# OBC.net
KiCad netlist of a schematic drawn in EAGLE
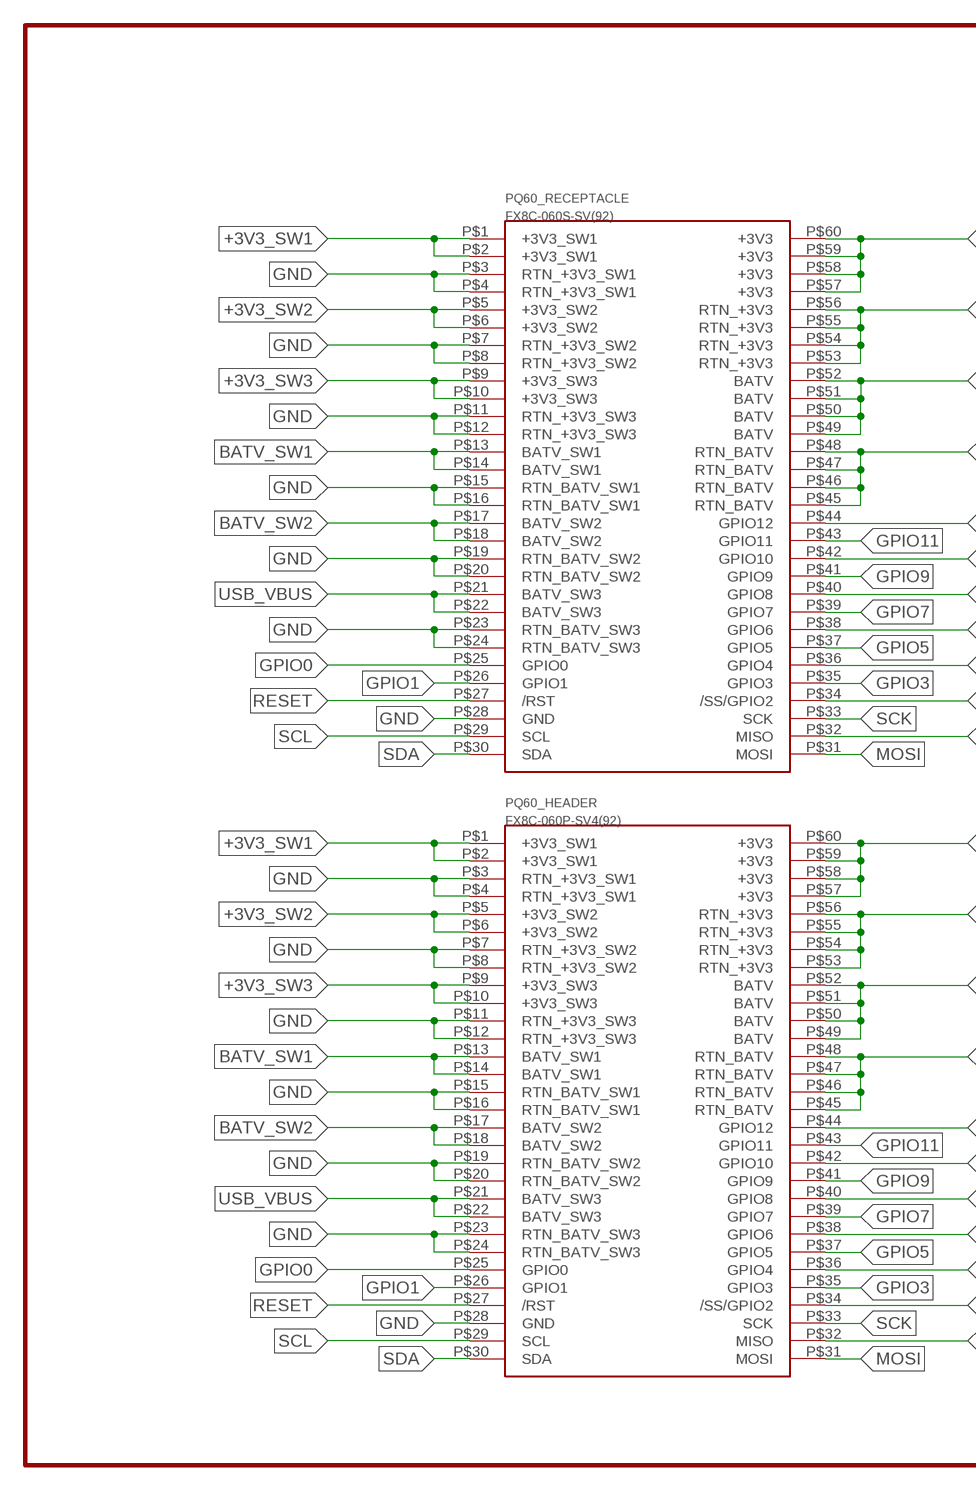
[diagram p0: schematic, sheet 1, part 1 of 2]
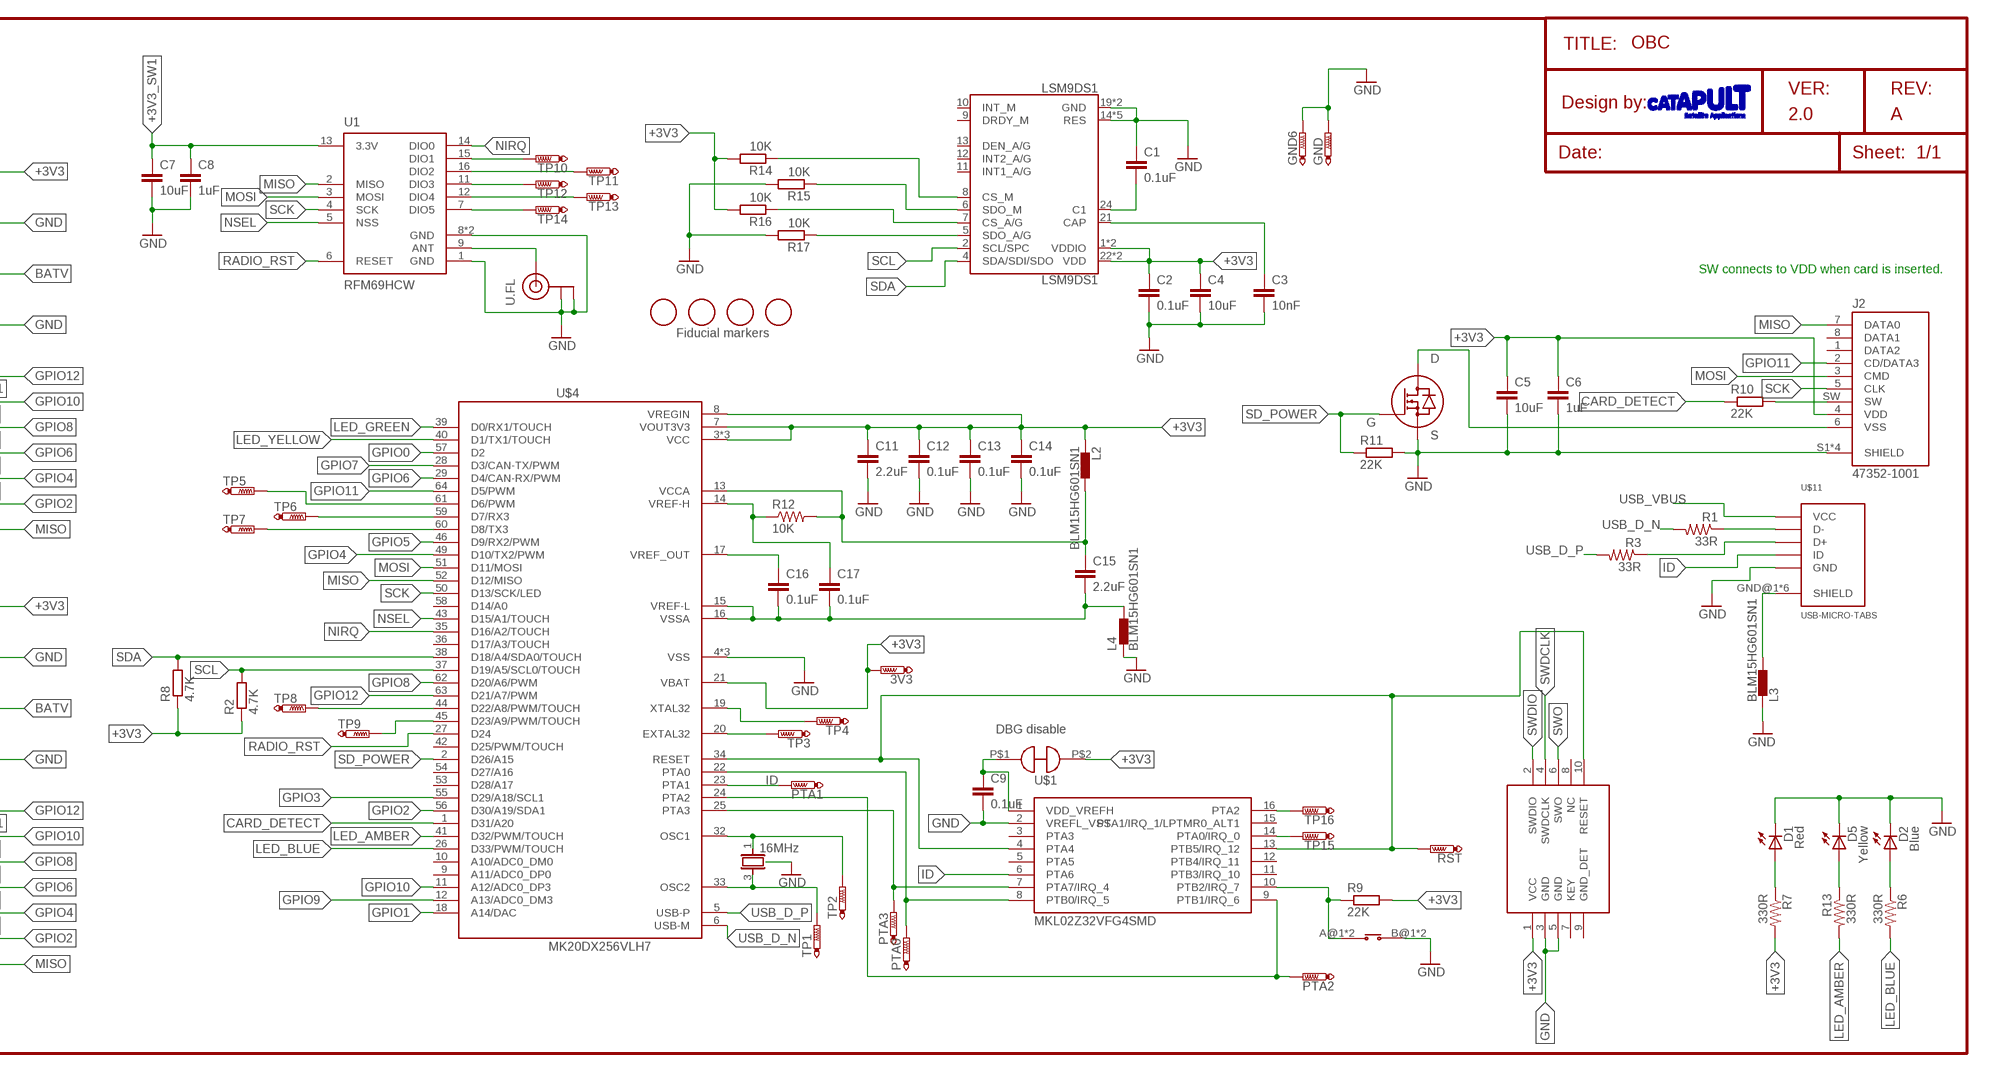
[diagram p1: schematic, sheet 1, part 2 of 2]

(export (version "E")
  (design (tool "Eeschema 10.0.6"))
  (components
    (comp (ref "3V3")
      (value "PTR1TP06R")
      (footprint "eagle-import:TP06R")
      (libsource (lib "eagle-import") (part "PTR1TP06R"))
    )
    (comp (ref "C1")
      (value "0.1uF")
      (footprint "eagle-import:C0402")
      (libsource (lib "eagle-import") (part "C-EUC0402"))
    )
    (comp (ref "C2")
      (value "0.1uF")
      (footprint "eagle-import:C0402")
      (libsource (lib "eagle-import") (part "C-EUC0402"))
    )
    (comp (ref "C3")
      (value "10nF")
      (footprint "eagle-import:C0402")
      (libsource (lib "eagle-import") (part "C-EUC0402"))
    )
    (comp (ref "C4")
      (value "10uF")
      (footprint "eagle-import:C0805")
      (libsource (lib "eagle-import") (part "C-EUC0805"))
    )
    (comp (ref "C5")
      (value "10uF")
      (footprint "eagle-import:C0805")
      (libsource (lib "eagle-import") (part "C-EUC0805"))
    )
    (comp (ref "C6")
      (value "1uF")
      (footprint "eagle-import:C0603")
      (libsource (lib "eagle-import") (part "C-EUC0603"))
    )
    (comp (ref "C7")
      (value "10uF")
      (footprint "eagle-import:C0805")
      (libsource (lib "eagle-import") (part "C-EUC0805"))
    )
    (comp (ref "C8")
      (value "1uF")
      (footprint "eagle-import:C0603")
      (libsource (lib "eagle-import") (part "C-EUC0603"))
    )
    (comp (ref "C9")
      (value "0.1uF")
      (footprint "eagle-import:C0402")
      (libsource (lib "eagle-import") (part "C-EUC0402"))
    )
    (comp (ref "C11")
      (value "2.2uF")
      (footprint "eagle-import:C0603")
      (libsource (lib "eagle-import") (part "C-EUC0603"))
    )
    (comp (ref "C12")
      (value "0.1uF")
      (footprint "eagle-import:C0402")
      (libsource (lib "eagle-import") (part "C-EUC0402"))
    )
    (comp (ref "C13")
      (value "0.1uF")
      (footprint "eagle-import:C0402")
      (libsource (lib "eagle-import") (part "C-EUC0402"))
    )
    (comp (ref "C14")
      (value "0.1uF")
      (footprint "eagle-import:C0402")
      (libsource (lib "eagle-import") (part "C-EUC0402"))
    )
    (comp (ref "C15")
      (value "2.2uF")
      (footprint "eagle-import:C0603")
      (libsource (lib "eagle-import") (part "C-EUC0603"))
    )
    (comp (ref "C16")
      (value "0.1uF")
      (footprint "eagle-import:C0402")
      (libsource (lib "eagle-import") (part "C-EUC0402"))
    )
    (comp (ref "C17")
      (value "0.1uF")
      (footprint "eagle-import:C0402")
      (libsource (lib "eagle-import") (part "C-EUC0402"))
    )
    (comp (ref "D1")
      (value "Red")
      (footprint "eagle-import:CHIPLED_0603")
      (libsource (lib "eagle-import") (part "LEDCHIPLED_0603"))
    )
    (comp (ref "D2")
      (value "Blue")
      (footprint "eagle-import:CHIPLED_0603")
      (libsource (lib "eagle-import") (part "LEDCHIPLED_0603"))
    )
    (comp (ref "D5")
      (value "Yellow")
      (footprint "eagle-import:CHIPLED_0603")
      (libsource (lib "eagle-import") (part "LEDCHIPLED_0603"))
    )
    (comp (ref "ERASE")
      (value "EVPAF7B70")
      (footprint "eagle-import:EVPAF7B70")
      (libsource (lib "eagle-import") (part "EVPAF7B70"))
    )
    (comp (ref "FD1")
      (value "FIDUCIAL")
      (footprint "eagle-import:FIDUCIAL_1MM")
      (libsource (lib "eagle-import") (part "FIDUCIAL"))
    )
    (comp (ref "FD2")
      (value "FIDUCIAL")
      (footprint "eagle-import:FIDUCIAL_1MM")
      (libsource (lib "eagle-import") (part "FIDUCIAL"))
    )
    (comp (ref "FD3")
      (value "FIDUCIAL")
      (footprint "eagle-import:FIDUCIAL_1MM")
      (libsource (lib "eagle-import") (part "FIDUCIAL"))
    )
    (comp (ref "FD4")
      (value "FIDUCIAL")
      (footprint "eagle-import:FIDUCIAL_1MM")
      (libsource (lib "eagle-import") (part "FIDUCIAL"))
    )
    (comp (ref "GND")
      (value "PTR1TP06R")
      (footprint "eagle-import:TP06R")
      (libsource (lib "eagle-import") (part "PTR1TP06R"))
    )
    (comp (ref "GND6")
      (value "PTR1TP06R")
      (footprint "eagle-import:TP06R")
      (libsource (lib "eagle-import") (part "PTR1TP06R"))
    )
    (comp (ref "J2")
      (value "47352-1001")
      (footprint "eagle-import:MOLEX_47352-1001")
      (fields (field (name "MF") "Molex") (field (name "MP") "473521001"))
      (libsource (lib "eagle-import") (part "47352-1001"))
    )
    (comp (ref "L2")
      (value "BLM15HG601SN1")
      (footprint "eagle-import:0402")
      (libsource (lib "eagle-import") (part "BLM15HG601SN1"))
    )
    (comp (ref "L3")
      (value "BLM15HG601SN1")
      (footprint "eagle-import:0402")
      (libsource (lib "eagle-import") (part "BLM15HG601SN1"))
    )
    (comp (ref "L4")
      (value "BLM15HG601SN1")
      (footprint "eagle-import:0402")
      (libsource (lib "eagle-import") (part "BLM15HG601SN1"))
    )
    (comp (ref "LSM9DS1")
      (value "LSM9DS1")
      (footprint "eagle-import:LGA24-8X4")
      (libsource (lib "eagle-import") (part "LSM9DS1"))
    )
    (comp (ref "NDK_NX3225SA")
      (value "16MHz")
      (footprint "eagle-import:4SMD_DFN_LCC")
      (libsource (lib "eagle-import") (part "NDKCRYSTAL"))
    )
    (comp (ref "PQ60_HEADER")
      (value "FX8C-060P-SV4(92)")
      (footprint "eagle-import:FX8C-060P-SV4(92)")
      (libsource (lib "eagle-import") (part "FX8C-060P-SV4(92)"))
    )
    (comp (ref "PQ60_RECEPTACLE")
      (value "FX8C-060S-SV(92)")
      (footprint "eagle-import:FX8C-060S-SV(92)")
      (libsource (lib "eagle-import") (part "FX8C-060S-SV(92)"))
    )
    (comp (ref "PTA0")
      (value "PTR1TP06R")
      (footprint "eagle-import:TP06R")
      (libsource (lib "eagle-import") (part "PTR1TP06R"))
    )
    (comp (ref "PTA1")
      (value "PTR1TP06R")
      (footprint "eagle-import:TP06R")
      (libsource (lib "eagle-import") (part "PTR1TP06R"))
    )
    (comp (ref "PTA2")
      (value "PTR1TP06R")
      (footprint "eagle-import:TP06R")
      (libsource (lib "eagle-import") (part "PTR1TP06R"))
    )
    (comp (ref "PTA3")
      (value "PTR1TP06R")
      (footprint "eagle-import:TP06R")
      (libsource (lib "eagle-import") (part "PTR1TP06R"))
    )
    (comp (ref "R1")
      (value "33R")
      (footprint "eagle-import:0603-RES")
      (libsource (lib "eagle-import") (part "RESISTOR0603-RES"))
    )
    (comp (ref "R2")
      (value "4.7K")
      (footprint "eagle-import:R0402")
      (libsource (lib "eagle-import") (part "R-EU_R0402"))
    )
    (comp (ref "R3")
      (value "33R")
      (footprint "eagle-import:0603-RES")
      (libsource (lib "eagle-import") (part "RESISTOR0603-RES"))
    )
    (comp (ref "R6")
      (value "330R")
      (footprint "eagle-import:0603-RES")
      (libsource (lib "eagle-import") (part "RESISTOR0603-RES"))
    )
    (comp (ref "R7")
      (value "330R")
      (footprint "eagle-import:0603-RES")
      (libsource (lib "eagle-import") (part "RESISTOR0603-RES"))
    )
    (comp (ref "R8")
      (value "4.7K")
      (footprint "eagle-import:R0402")
      (libsource (lib "eagle-import") (part "R-EU_R0402"))
    )
    (comp (ref "R9")
      (value "22K")
      (footprint "eagle-import:R0402")
      (libsource (lib "eagle-import") (part "R-EU_R0402"))
    )
    (comp (ref "R10")
      (value "22K")
      (footprint "eagle-import:R0402")
      (libsource (lib "eagle-import") (part "R-EU_R0402"))
    )
    (comp (ref "R11")
      (value "22K")
      (footprint "eagle-import:R0402")
      (libsource (lib "eagle-import") (part "R-EU_R0402"))
    )
    (comp (ref "R12")
      (value "10K")
      (footprint "eagle-import:0402-RES")
      (libsource (lib "eagle-import") (part "RESISTOR0402-RES"))
    )
    (comp (ref "R13")
      (value "330R")
      (footprint "eagle-import:0603-RES")
      (libsource (lib "eagle-import") (part "RESISTOR0603-RES"))
    )
    (comp (ref "R14")
      (value "10K")
      (footprint "eagle-import:R0402")
      (libsource (lib "eagle-import") (part "R-EU_R0402"))
    )
    (comp (ref "R15")
      (value "10K")
      (footprint "eagle-import:R0402")
      (libsource (lib "eagle-import") (part "R-EU_R0402"))
    )
    (comp (ref "R16")
      (value "10K")
      (footprint "eagle-import:R0402")
      (libsource (lib "eagle-import") (part "R-EU_R0402"))
    )
    (comp (ref "R17")
      (value "10K")
      (footprint "eagle-import:R0402")
      (libsource (lib "eagle-import") (part "R-EU_R0402"))
    )
    (comp (ref "RST")
      (value "PTR1TP06R")
      (footprint "eagle-import:TP06R")
      (libsource (lib "eagle-import") (part "PTR1TP06R"))
    )
    (comp (ref "SJ3")
      (value "SJNC")
      (footprint "eagle-import:SJNC")
      (libsource (lib "eagle-import") (part "SJNC"))
    )
    (comp (ref "TP1")
      (value "PTR1TP06R")
      (footprint "eagle-import:TP06R")
      (libsource (lib "eagle-import") (part "PTR1TP06R"))
    )
    (comp (ref "TP2")
      (value "PTR1TP06R")
      (footprint "eagle-import:TP06R")
      (libsource (lib "eagle-import") (part "PTR1TP06R"))
    )
    (comp (ref "TP3")
      (value "PTR1TP06R")
      (footprint "eagle-import:TP06R")
      (libsource (lib "eagle-import") (part "PTR1TP06R"))
    )
    (comp (ref "TP4")
      (value "PTR1TP06R")
      (footprint "eagle-import:TP06R")
      (libsource (lib "eagle-import") (part "PTR1TP06R"))
    )
    (comp (ref "TP5")
      (value "PTR1TP06R")
      (footprint "eagle-import:TP06R")
      (libsource (lib "eagle-import") (part "PTR1TP06R"))
    )
    (comp (ref "TP6")
      (value "PTR1TP06R")
      (footprint "eagle-import:TP06R")
      (libsource (lib "eagle-import") (part "PTR1TP06R"))
    )
    (comp (ref "TP7")
      (value "PTR1TP06R")
      (footprint "eagle-import:TP06R")
      (libsource (lib "eagle-import") (part "PTR1TP06R"))
    )
    (comp (ref "TP8")
      (value "PTR1TP06R")
      (footprint "eagle-import:TP06R")
      (libsource (lib "eagle-import") (part "PTR1TP06R"))
    )
    (comp (ref "TP9")
      (value "PTR1TP06R")
      (footprint "eagle-import:TP06R")
      (libsource (lib "eagle-import") (part "PTR1TP06R"))
    )
    (comp (ref "TP10")
      (value "PTR1TP06R")
      (footprint "eagle-import:TP06R")
      (libsource (lib "eagle-import") (part "PTR1TP06R"))
    )
    (comp (ref "TP11")
      (value "PTR1TP06R")
      (footprint "eagle-import:TP06R")
      (libsource (lib "eagle-import") (part "PTR1TP06R"))
    )
    (comp (ref "TP12")
      (value "PTR1TP06R")
      (footprint "eagle-import:TP06R")
      (libsource (lib "eagle-import") (part "PTR1TP06R"))
    )
    (comp (ref "TP13")
      (value "PTR1TP06R")
      (footprint "eagle-import:TP06R")
      (libsource (lib "eagle-import") (part "PTR1TP06R"))
    )
    (comp (ref "TP14")
      (value "PTR1TP06R")
      (footprint "eagle-import:TP06R")
      (libsource (lib "eagle-import") (part "PTR1TP06R"))
    )
    (comp (ref "TP15")
      (value "PTR1TP06R")
      (footprint "eagle-import:TP06R")
      (libsource (lib "eagle-import") (part "PTR1TP06R"))
    )
    (comp (ref "TP16")
      (value "PTR1TP06R")
      (footprint "eagle-import:TP06R")
      (libsource (lib "eagle-import") (part "PTR1TP06R"))
    )
    (comp (ref "U$1")
      (value "MKL02Z32VFG4SMD")
      (footprint "eagle-import:QFN16")
      (libsource (lib "eagle-import") (part "MKL02Z32VFG4SMD"))
    )
    (comp (ref "U$3")
      (value "PMV40UN2")
      (footprint "eagle-import:SOT23-3")
      (libsource (lib "eagle-import") (part "PMV40UN2"))
    )
    (comp (ref "U$4")
      (value "MK20DX256VLH7")
      (footprint "eagle-import:QFP50P1200X1200X160-64N")
      (libsource (lib "eagle-import") (part "MK20DX256VLH7"))
    )
    (comp (ref "U$9")
      (value "SWD_10_PIN")
      (footprint "eagle-import:SWD_10_PIN")
      (libsource (lib "eagle-import") (part "SWD_10_PIN"))
    )
    (comp (ref "U$11")
      (value "USB-MICRO-TABS")
      (footprint "eagle-import:USB-MICRO-TABS")
      (libsource (lib "eagle-import") (part "USB-MICRO-TABS"))
    )
    (comp (ref "U.FL")
      (value "U.FL")
      (footprint "eagle-import:U.FL")
      (libsource (lib "eagle-import") (part "U.FL"))
    )
    (comp (ref "U1")
      (value "RFM69HCW")
      (footprint "eagle-import:RFM69HCW-XXXS2")
      (libsource (lib "eagle-import") (part "RFM69HCW"))
    )
  )
  (nets
    (net (code "1") (name "+3V3") (class "Default")
      (node (ref "3V3") (pin "TP") (pinfunction "TP_TP") (pintype "input"))
      (node (ref "C11") (pin "1") (pinfunction "1_1") (pintype "passive"))
      (node (ref "C12") (pin "1") (pinfunction "1_1") (pintype "passive"))
      (node (ref "C13") (pin "1") (pinfunction "1_1") (pintype "passive"))
      (node (ref "C14") (pin "1") (pinfunction "1_1") (pintype "passive"))
      (node (ref "C2") (pin "1") (pinfunction "1_1") (pintype "passive"))
      (node (ref "C4") (pin "1") (pinfunction "1_1") (pintype "passive"))
      (node (ref "C5") (pin "1") (pinfunction "1_1") (pintype "passive"))
      (node (ref "C6") (pin "1") (pinfunction "1_1") (pintype "passive"))
      (node (ref "J2") (pin "4") (pinfunction "VDD_4") (pintype "passive"))
      (node (ref "L2") (pin "1") (pinfunction "1_1") (pintype "passive"))
      (node (ref "LSM9DS1") (pin "1") (pinfunction "VDDIO_1") (pintype "bidirectional"))
      (node (ref "LSM9DS1") (pin "22") (pinfunction "VDD_22") (pintype "bidirectional"))
      (node (ref "LSM9DS1") (pin "23") (pinfunction "VDD_23") (pintype "bidirectional"))
      (node (ref "LSM9DS1") (pin "3") (pinfunction "VDDIO_3") (pintype "bidirectional"))
      (node (ref "PQ60_HEADER") (pin "P$57") (pinfunction "+3V3_P$57") (pintype "power_in"))
      (node (ref "PQ60_HEADER") (pin "P$58") (pinfunction "+3V3_P$58") (pintype "power_in"))
      (node (ref "PQ60_HEADER") (pin "P$59") (pinfunction "+3V3_P$59") (pintype "power_in"))
      (node (ref "PQ60_HEADER") (pin "P$60") (pinfunction "+3V3_P$60") (pintype "power_in"))
      (node (ref "PQ60_RECEPTACLE") (pin "P$57") (pinfunction "+3V3_P$57") (pintype "power_in"))
      (node (ref "PQ60_RECEPTACLE") (pin "P$58") (pinfunction "+3V3_P$58") (pintype "power_in"))
      (node (ref "PQ60_RECEPTACLE") (pin "P$59") (pinfunction "+3V3_P$59") (pintype "power_in"))
      (node (ref "PQ60_RECEPTACLE") (pin "P$60") (pinfunction "+3V3_P$60") (pintype "power_in"))
      (node (ref "R14") (pin "2") (pinfunction "2_2") (pintype "passive"))
      (node (ref "R16") (pin "2") (pinfunction "2_2") (pintype "passive"))
      (node (ref "R2") (pin "1") (pinfunction "1_1") (pintype "passive"))
      (node (ref "R7") (pin "2") (pinfunction "2_2") (pintype "passive"))
      (node (ref "R8") (pin "1") (pinfunction "1_1") (pintype "passive"))
      (node (ref "R9") (pin "2") (pinfunction "2_2") (pintype "passive"))
      (node (ref "SJ3") (pin "P$2") (pinfunction "P$2_P$2") (pintype "bidirectional"))
      (node (ref "U$4") (pin "21") (pinfunction "VBAT_21") (pintype "bidirectional"))
      (node (ref "U$4") (pin "3") (pinfunction "VCC_3") (pintype "bidirectional"))
      (node (ref "U$4") (pin "30") (pinfunction "VCC_30") (pintype "bidirectional"))
      (node (ref "U$4") (pin "48") (pinfunction "VCC_48") (pintype "bidirectional"))
      (node (ref "U$4") (pin "7") (pinfunction "VOUT3V3_7") (pintype "bidirectional"))
      (node (ref "U$4") (pin "8") (pinfunction "VREGIN_8") (pintype "bidirectional"))
      (node (ref "U$9") (pin "1") (pinfunction "VCC_1") (pintype "bidirectional"))
    )
    (net (code "2") (name "+3V3_SW1") (class "Default")
      (node (ref "C7") (pin "1") (pinfunction "1_1") (pintype "passive"))
      (node (ref "C8") (pin "1") (pinfunction "1_1") (pintype "passive"))
      (node (ref "PQ60_HEADER") (pin "P$1") (pinfunction "+3V3_SW1_P$1") (pintype "power_in"))
      (node (ref "PQ60_HEADER") (pin "P$2") (pinfunction "+3V3_SW1_P$2") (pintype "power_in"))
      (node (ref "PQ60_RECEPTACLE") (pin "P$1") (pinfunction "+3V3_SW1_P$1") (pintype "power_in"))
      (node (ref "PQ60_RECEPTACLE") (pin "P$2") (pinfunction "+3V3_SW1_P$2") (pintype "power_in"))
      (node (ref "U1") (pin "13") (pinfunction "3.3V_13") (pintype "power_in"))
    )
    (net (code "3") (name "+3V3_SW2") (class "Default")
      (node (ref "PQ60_HEADER") (pin "P$5") (pinfunction "+3V3_SW2_P$5") (pintype "power_in"))
      (node (ref "PQ60_HEADER") (pin "P$6") (pinfunction "+3V3_SW2_P$6") (pintype "power_in"))
      (node (ref "PQ60_RECEPTACLE") (pin "P$5") (pinfunction "+3V3_SW2_P$5") (pintype "power_in"))
      (node (ref "PQ60_RECEPTACLE") (pin "P$6") (pinfunction "+3V3_SW2_P$6") (pintype "power_in"))
    )
    (net (code "4") (name "+3V3_SW3") (class "Default")
      (node (ref "PQ60_HEADER") (pin "P$10") (pinfunction "+3V3_SW3_P$10") (pintype "power_in"))
      (node (ref "PQ60_HEADER") (pin "P$9") (pinfunction "+3V3_SW3_P$9") (pintype "power_in"))
      (node (ref "PQ60_RECEPTACLE") (pin "P$10") (pinfunction "+3V3_SW3_P$10") (pintype "power_in"))
      (node (ref "PQ60_RECEPTACLE") (pin "P$9") (pinfunction "+3V3_SW3_P$9") (pintype "power_in"))
    )
    (net (code "5") (name "BATV") (class "Default")
      (node (ref "PQ60_HEADER") (pin "P$49") (pinfunction "BATV_P$49") (pintype "power_in"))
      (node (ref "PQ60_HEADER") (pin "P$50") (pinfunction "BATV_P$50") (pintype "power_in"))
      (node (ref "PQ60_HEADER") (pin "P$51") (pinfunction "BATV_P$51") (pintype "power_in"))
      (node (ref "PQ60_HEADER") (pin "P$52") (pinfunction "BATV_P$52") (pintype "power_in"))
      (node (ref "PQ60_RECEPTACLE") (pin "P$49") (pinfunction "BATV_P$49") (pintype "power_in"))
      (node (ref "PQ60_RECEPTACLE") (pin "P$50") (pinfunction "BATV_P$50") (pintype "power_in"))
      (node (ref "PQ60_RECEPTACLE") (pin "P$51") (pinfunction "BATV_P$51") (pintype "power_in"))
      (node (ref "PQ60_RECEPTACLE") (pin "P$52") (pinfunction "BATV_P$52") (pintype "power_in"))
    )
    (net (code "6") (name "BATV_SW1") (class "Default")
      (node (ref "PQ60_HEADER") (pin "P$13") (pinfunction "BATV_SW1_P$13") (pintype "power_in"))
      (node (ref "PQ60_HEADER") (pin "P$14") (pinfunction "BATV_SW1_P$14") (pintype "power_in"))
      (node (ref "PQ60_RECEPTACLE") (pin "P$13") (pinfunction "BATV_SW1_P$13") (pintype "power_in"))
      (node (ref "PQ60_RECEPTACLE") (pin "P$14") (pinfunction "BATV_SW1_P$14") (pintype "power_in"))
    )
    (net (code "7") (name "BATV_SW2") (class "Default")
      (node (ref "PQ60_HEADER") (pin "P$17") (pinfunction "BATV_SW2_P$17") (pintype "power_in"))
      (node (ref "PQ60_HEADER") (pin "P$18") (pinfunction "BATV_SW2_P$18") (pintype "power_in"))
      (node (ref "PQ60_RECEPTACLE") (pin "P$17") (pinfunction "BATV_SW2_P$17") (pintype "power_in"))
      (node (ref "PQ60_RECEPTACLE") (pin "P$18") (pinfunction "BATV_SW2_P$18") (pintype "power_in"))
    )
    (net (code "8") (name "CARD_DETECT") (class "Default")
      (node (ref "R10") (pin "1") (pinfunction "1_1") (pintype "passive"))
      (node (ref "U$4") (pin "1") (pinfunction "D31/A20_1") (pintype "bidirectional"))
    )
    (net (code "9") (name "GND") (class "Default")
      (node (ref "C1") (pin "1") (pinfunction "1_1") (pintype "passive"))
      (node (ref "C11") (pin "2") (pinfunction "2_2") (pintype "passive"))
      (node (ref "C12") (pin "2") (pinfunction "2_2") (pintype "passive"))
      (node (ref "C13") (pin "2") (pinfunction "2_2") (pintype "passive"))
      (node (ref "C14") (pin "2") (pinfunction "2_2") (pintype "passive"))
      (node (ref "C2") (pin "2") (pinfunction "2_2") (pintype "passive"))
      (node (ref "C3") (pin "2") (pinfunction "2_2") (pintype "passive"))
      (node (ref "C4") (pin "2") (pinfunction "2_2") (pintype "passive"))
      (node (ref "C5") (pin "2") (pinfunction "2_2") (pintype "passive"))
      (node (ref "C6") (pin "2") (pinfunction "2_2") (pintype "passive"))
      (node (ref "C7") (pin "2") (pinfunction "2_2") (pintype "passive"))
      (node (ref "C8") (pin "2") (pinfunction "2_2") (pintype "passive"))
      (node (ref "C9") (pin "2") (pinfunction "2_2") (pintype "passive"))
      (node (ref "D1") (pin "C") (pinfunction "C_C") (pintype "passive"))
      (node (ref "D2") (pin "C") (pinfunction "C_C") (pintype "passive"))
      (node (ref "D5") (pin "C") (pinfunction "C_C") (pintype "passive"))
      (node (ref "ERASE") (pin "B@1") (pinfunction "P$2_B@1") (pintype "bidirectional"))
      (node (ref "ERASE") (pin "B@2") (pinfunction "P$2_B@2") (pintype "bidirectional"))
      (node (ref "GND") (pin "TP") (pinfunction "TP_TP") (pintype "input"))
      (node (ref "GND6") (pin "TP") (pinfunction "TP_TP") (pintype "input"))
      (node (ref "J2") (pin "S1") (pinfunction "SHIELD_S1") (pintype "passive"))
      (node (ref "J2") (pin "S2") (pinfunction "SHIELD_S2") (pintype "passive"))
      (node (ref "J2") (pin "S3") (pinfunction "SHIELD_S3") (pintype "passive"))
      (node (ref "J2") (pin "S4") (pinfunction "SHIELD_S4") (pintype "passive"))
      (node (ref "L3") (pin "1") (pinfunction "1_1") (pintype "passive"))
      (node (ref "L4") (pin "1") (pinfunction "1_1") (pintype "passive"))
      (node (ref "LSM9DS1") (pin "14") (pinfunction "RES_14") (pintype "bidirectional"))
      (node (ref "LSM9DS1") (pin "15") (pinfunction "RES_15") (pintype "bidirectional"))
      (node (ref "LSM9DS1") (pin "16") (pinfunction "RES_16") (pintype "bidirectional"))
      (node (ref "LSM9DS1") (pin "17") (pinfunction "RES_17") (pintype "bidirectional"))
      (node (ref "LSM9DS1") (pin "18") (pinfunction "RES_18") (pintype "bidirectional"))
      (node (ref "LSM9DS1") (pin "19") (pinfunction "GND_19") (pintype "bidirectional"))
      (node (ref "LSM9DS1") (pin "20") (pinfunction "GND_20") (pintype "bidirectional"))
      (node (ref "NDK_NX3225SA") (pin "GND") (pinfunction "GND_GND") (pintype "bidirectional"))
      (node (ref "NDK_NX3225SA") (pin "GND@1") (pinfunction "GND_GND@1") (pintype "bidirectional"))
      (node (ref "NDK_NX3225SA") (pin "GND@2") (pinfunction "GND_GND@2") (pintype "bidirectional"))
      (node (ref "PQ60_HEADER") (pin "P$11") (pinfunction "RTN_+3V3_SW3_P$11") (pintype "power_in"))
      (node (ref "PQ60_HEADER") (pin "P$12") (pinfunction "RTN_+3V3_SW3_P$12") (pintype "power_in"))
      (node (ref "PQ60_HEADER") (pin "P$15") (pinfunction "RTN_BATV_SW1_P$15") (pintype "power_in"))
      (node (ref "PQ60_HEADER") (pin "P$16") (pinfunction "RTN_BATV_SW1_P$16") (pintype "power_in"))
      (node (ref "PQ60_HEADER") (pin "P$19") (pinfunction "RTN_BATV_SW2_P$19") (pintype "power_in"))
      (node (ref "PQ60_HEADER") (pin "P$20") (pinfunction "RTN_BATV_SW2_P$20") (pintype "power_in"))
      (node (ref "PQ60_HEADER") (pin "P$23") (pinfunction "RTN_BATV_SW3_P$23") (pintype "power_in"))
      (node (ref "PQ60_HEADER") (pin "P$24") (pinfunction "RTN_BATV_SW3_P$24") (pintype "power_in"))
      (node (ref "PQ60_HEADER") (pin "P$28") (pinfunction "GND_P$28") (pintype "bidirectional"))
      (node (ref "PQ60_HEADER") (pin "P$3") (pinfunction "RTN_+3V3_SW1_P$3") (pintype "power_in"))
      (node (ref "PQ60_HEADER") (pin "P$4") (pinfunction "RTN_+3V3_SW1_P$4") (pintype "power_in"))
      (node (ref "PQ60_HEADER") (pin "P$45") (pinfunction "RTN_BATV_P$45") (pintype "power_in"))
      (node (ref "PQ60_HEADER") (pin "P$46") (pinfunction "RTN_BATV_P$46") (pintype "power_in"))
      (node (ref "PQ60_HEADER") (pin "P$47") (pinfunction "RTN_BATV_P$47") (pintype "power_in"))
      (node (ref "PQ60_HEADER") (pin "P$48") (pinfunction "RTN_BATV_P$48") (pintype "power_in"))
      (node (ref "PQ60_HEADER") (pin "P$53") (pinfunction "RTN_+3V3_P$53") (pintype "power_in"))
      (node (ref "PQ60_HEADER") (pin "P$54") (pinfunction "RTN_+3V3_P$54") (pintype "power_in"))
      (node (ref "PQ60_HEADER") (pin "P$55") (pinfunction "RTN_+3V3_P$55") (pintype "power_in"))
      (node (ref "PQ60_HEADER") (pin "P$56") (pinfunction "RTN_+3V3_P$56") (pintype "power_in"))
      (node (ref "PQ60_HEADER") (pin "P$7") (pinfunction "RTN_+3V3_SW2_P$7") (pintype "power_in"))
      (node (ref "PQ60_HEADER") (pin "P$8") (pinfunction "RTN_+3V3_SW2_P$8") (pintype "power_in"))
      (node (ref "PQ60_RECEPTACLE") (pin "P$11") (pinfunction "RTN_+3V3_SW3_P$11") (pintype "power_in"))
      (node (ref "PQ60_RECEPTACLE") (pin "P$12") (pinfunction "RTN_+3V3_SW3_P$12") (pintype "power_in"))
      (node (ref "PQ60_RECEPTACLE") (pin "P$15") (pinfunction "RTN_BATV_SW1_P$15") (pintype "power_in"))
      (node (ref "PQ60_RECEPTACLE") (pin "P$16") (pinfunction "RTN_BATV_SW1_P$16") (pintype "power_in"))
      (node (ref "PQ60_RECEPTACLE") (pin "P$19") (pinfunction "RTN_BATV_SW2_P$19") (pintype "power_in"))
      (node (ref "PQ60_RECEPTACLE") (pin "P$20") (pinfunction "RTN_BATV_SW2_P$20") (pintype "power_in"))
      (node (ref "PQ60_RECEPTACLE") (pin "P$23") (pinfunction "RTN_BATV_SW3_P$23") (pintype "power_in"))
      (node (ref "PQ60_RECEPTACLE") (pin "P$24") (pinfunction "RTN_BATV_SW3_P$24") (pintype "power_in"))
      (node (ref "PQ60_RECEPTACLE") (pin "P$28") (pinfunction "GND_P$28") (pintype "bidirectional"))
      (node (ref "PQ60_RECEPTACLE") (pin "P$3") (pinfunction "RTN_+3V3_SW1_P$3") (pintype "power_in"))
      (node (ref "PQ60_RECEPTACLE") (pin "P$4") (pinfunction "RTN_+3V3_SW1_P$4") (pintype "power_in"))
      (node (ref "PQ60_RECEPTACLE") (pin "P$45") (pinfunction "RTN_BATV_P$45") (pintype "power_in"))
      (node (ref "PQ60_RECEPTACLE") (pin "P$46") (pinfunction "RTN_BATV_P$46") (pintype "power_in"))
      (node (ref "PQ60_RECEPTACLE") (pin "P$47") (pinfunction "RTN_BATV_P$47") (pintype "power_in"))
      (node (ref "PQ60_RECEPTACLE") (pin "P$48") (pinfunction "RTN_BATV_P$48") (pintype "power_in"))
      (node (ref "PQ60_RECEPTACLE") (pin "P$53") (pinfunction "RTN_+3V3_P$53") (pintype "power_in"))
      (node (ref "PQ60_RECEPTACLE") (pin "P$54") (pinfunction "RTN_+3V3_P$54") (pintype "power_in"))
      (node (ref "PQ60_RECEPTACLE") (pin "P$55") (pinfunction "RTN_+3V3_P$55") (pintype "power_in"))
      (node (ref "PQ60_RECEPTACLE") (pin "P$56") (pinfunction "RTN_+3V3_P$56") (pintype "power_in"))
      (node (ref "PQ60_RECEPTACLE") (pin "P$7") (pinfunction "RTN_+3V3_SW2_P$7") (pintype "power_in"))
      (node (ref "PQ60_RECEPTACLE") (pin "P$8") (pinfunction "RTN_+3V3_SW2_P$8") (pintype "power_in"))
      (node (ref "R11") (pin "2") (pinfunction "2_2") (pintype "passive"))
      (node (ref "R15") (pin "2") (pinfunction "2_2") (pintype "passive"))
      (node (ref "R17") (pin "2") (pinfunction "2_2") (pintype "passive"))
      (node (ref "U$1") (pin "2") (pinfunction "VREFL_VSS_2") (pintype "bidirectional"))
      (node (ref "U$11") (pin "PIN$5") (pinfunction "GND_PIN$5") (pintype "bidirectional"))
      (node (ref "U$3") (pin "2") (pinfunction "S_2") (pintype "bidirectional"))
      (node (ref "U$4") (pin "31") (pinfunction "VSS_31") (pintype "bidirectional"))
      (node (ref "U$4") (pin "4") (pinfunction "VSS_4") (pintype "bidirectional"))
      (node (ref "U$4") (pin "47") (pinfunction "VSS_47") (pintype "bidirectional"))
      (node (ref "U$9") (pin "3") (pinfunction "GND_3") (pintype "bidirectional"))
      (node (ref "U$9") (pin "5") (pinfunction "GND_5") (pintype "bidirectional"))
      (node (ref "U.FL") (pin "P$1") (pinfunction "GND_P$1") (pintype "bidirectional"))
      (node (ref "U.FL") (pin "P$2") (pinfunction "GND_P$2") (pintype "bidirectional"))
      (node (ref "U1") (pin "1") (pinfunction "GND_1") (pintype "power_in"))
      (node (ref "U1") (pin "10") (pinfunction "GND_10") (pintype "power_in"))
      (node (ref "U1") (pin "8") (pinfunction "GND_8") (pintype "power_in"))
    )
    (net (code "10") (name "GPIO0") (class "Default")
      (node (ref "PQ60_HEADER") (pin "P$25") (pinfunction "GPIO0_P$25") (pintype "bidirectional"))
      (node (ref "PQ60_RECEPTACLE") (pin "P$25") (pinfunction "GPIO0_P$25") (pintype "bidirectional"))
      (node (ref "U$4") (pin "57") (pinfunction "D2_57") (pintype "bidirectional"))
    )
    (net (code "11") (name "GPIO1") (class "Default")
      (node (ref "PQ60_HEADER") (pin "P$26") (pinfunction "GPIO1_P$26") (pintype "bidirectional"))
      (node (ref "PQ60_RECEPTACLE") (pin "P$26") (pinfunction "GPIO1_P$26") (pintype "bidirectional"))
      (node (ref "U$4") (pin "18") (pinfunction "A14/DAC_18") (pintype "bidirectional"))
    )
    (net (code "12") (name "GPIO2") (class "Default")
      (node (ref "PQ60_HEADER") (pin "P$34") (pinfunction "/SS/GPIO2_P$34") (pintype "bidirectional"))
      (node (ref "PQ60_RECEPTACLE") (pin "P$34") (pinfunction "/SS/GPIO2_P$34") (pintype "bidirectional"))
      (node (ref "U$4") (pin "56") (pinfunction "D30/A19/SDA1_56") (pintype "bidirectional"))
    )
    (net (code "13") (name "GPIO3") (class "Default")
      (node (ref "PQ60_HEADER") (pin "P$35") (pinfunction "GPIO3_P$35") (pintype "bidirectional"))
      (node (ref "PQ60_RECEPTACLE") (pin "P$35") (pinfunction "GPIO3_P$35") (pintype "bidirectional"))
      (node (ref "U$4") (pin "55") (pinfunction "D29/A18/SCL1_55") (pintype "bidirectional"))
    )
    (net (code "14") (name "GPIO4") (class "Default")
      (node (ref "PQ60_HEADER") (pin "P$36") (pinfunction "GPIO4_P$36") (pintype "bidirectional"))
      (node (ref "PQ60_RECEPTACLE") (pin "P$36") (pinfunction "GPIO4_P$36") (pintype "bidirectional"))
      (node (ref "U$4") (pin "49") (pinfunction "D10/TX2/PWM_49") (pintype "bidirectional"))
    )
    (net (code "15") (name "GPIO5") (class "Default")
      (node (ref "PQ60_HEADER") (pin "P$37") (pinfunction "GPIO5_P$37") (pintype "bidirectional"))
      (node (ref "PQ60_RECEPTACLE") (pin "P$37") (pinfunction "GPIO5_P$37") (pintype "bidirectional"))
      (node (ref "U$4") (pin "46") (pinfunction "D9/RX2/PWM_46") (pintype "bidirectional"))
    )
    (net (code "16") (name "GPIO6") (class "Default")
      (node (ref "PQ60_HEADER") (pin "P$38") (pinfunction "GPIO6_P$38") (pintype "bidirectional"))
      (node (ref "PQ60_RECEPTACLE") (pin "P$38") (pinfunction "GPIO6_P$38") (pintype "bidirectional"))
      (node (ref "U$4") (pin "29") (pinfunction "D4/CAN-RX/PWM_29") (pintype "bidirectional"))
    )
    (net (code "17") (name "GPIO7") (class "Default")
      (node (ref "PQ60_HEADER") (pin "P$39") (pinfunction "GPIO7_P$39") (pintype "bidirectional"))
      (node (ref "PQ60_RECEPTACLE") (pin "P$39") (pinfunction "GPIO7_P$39") (pintype "bidirectional"))
      (node (ref "U$4") (pin "28") (pinfunction "D3/CAN-TX/PWM_28") (pintype "bidirectional"))
    )
    (net (code "18") (name "GPIO8") (class "Default")
      (node (ref "PQ60_HEADER") (pin "P$40") (pinfunction "GPIO8_P$40") (pintype "bidirectional"))
      (node (ref "PQ60_RECEPTACLE") (pin "P$40") (pinfunction "GPIO8_P$40") (pintype "bidirectional"))
      (node (ref "U$4") (pin "62") (pinfunction "D20/A6/PWM_62") (pintype "bidirectional"))
    )
    (net (code "19") (name "GPIO9") (class "Default")
      (node (ref "PQ60_HEADER") (pin "P$41") (pinfunction "GPIO9_P$41") (pintype "bidirectional"))
      (node (ref "PQ60_RECEPTACLE") (pin "P$41") (pinfunction "GPIO9_P$41") (pintype "bidirectional"))
      (node (ref "U$4") (pin "12") (pinfunction "A13/ADC0_DM3_12") (pintype "bidirectional"))
    )
    (net (code "20") (name "GPIO10") (class "Default")
      (node (ref "PQ60_HEADER") (pin "P$42") (pinfunction "GPIO10_P$42") (pintype "bidirectional"))
      (node (ref "PQ60_RECEPTACLE") (pin "P$42") (pinfunction "GPIO10_P$42") (pintype "bidirectional"))
      (node (ref "U$4") (pin "11") (pinfunction "A12/ADC0_DP3_11") (pintype "bidirectional"))
    )
    (net (code "21") (name "GPIO11") (class "Default")
      (node (ref "J2") (pin "2") (pinfunction "CD/DATA3_2") (pintype "passive"))
      (node (ref "PQ60_HEADER") (pin "P$43") (pinfunction "GPIO11_P$43") (pintype "bidirectional"))
      (node (ref "PQ60_RECEPTACLE") (pin "P$43") (pinfunction "GPIO11_P$43") (pintype "bidirectional"))
      (node (ref "U$4") (pin "64") (pinfunction "D5/PWM_64") (pintype "bidirectional"))
    )
    (net (code "22") (name "GPIO12") (class "Default")
      (node (ref "PQ60_HEADER") (pin "P$44") (pinfunction "GPIO12_P$44") (pintype "bidirectional"))
      (node (ref "PQ60_RECEPTACLE") (pin "P$44") (pinfunction "GPIO12_P$44") (pintype "bidirectional"))
      (node (ref "U$4") (pin "63") (pinfunction "D21/A7/PWM_63") (pintype "bidirectional"))
    )
    (net (code "23") (name "ID") (class "Default")
      (node (ref "PTA1") (pin "TP") (pinfunction "TP_TP") (pintype "input"))
      (node (ref "U$1") (pin "6") (pinfunction "PTA6_6") (pintype "bidirectional"))
      (node (ref "U$11") (pin "P$4") (pinfunction "ID_P$4") (pintype "bidirectional"))
      (node (ref "U$4") (pin "23") (pinfunction "PTA1_23") (pintype "bidirectional"))
    )
    (net (code "24") (name "LED_AMBER") (class "Default")
      (node (ref "R13") (pin "2") (pinfunction "2_2") (pintype "passive"))
      (node (ref "U$4") (pin "41") (pinfunction "D32/PWM/TOUCH_41") (pintype "bidirectional"))
    )
    (net (code "25") (name "LED_BLUE") (class "Default")
      (node (ref "R6") (pin "2") (pinfunction "2_2") (pintype "passive"))
      (node (ref "U$4") (pin "26") (pinfunction "D33/PWM/TOUCH_26") (pintype "bidirectional"))
    )
    (net (code "26") (name "LED_GREEN") (class "Default")
      (node (ref "U$4") (pin "39") (pinfunction "D0/RX1/TOUCH_39") (pintype "bidirectional"))
    )
    (net (code "27") (name "LED_YELLOW") (class "Default")
      (node (ref "U$4") (pin "40") (pinfunction "D1/TX1/TOUCH_40") (pintype "bidirectional"))
    )
    (net (code "28") (name "MISO") (class "Default")
      (node (ref "J2") (pin "7") (pinfunction "DATA0_7") (pintype "passive"))
      (node (ref "PQ60_HEADER") (pin "P$32") (pinfunction "MISO_P$32") (pintype "bidirectional"))
      (node (ref "PQ60_RECEPTACLE") (pin "P$32") (pinfunction "MISO_P$32") (pintype "bidirectional"))
      (node (ref "U$4") (pin "52") (pinfunction "D12/MISO_52") (pintype "bidirectional"))
      (node (ref "U1") (pin "2") (pinfunction "MISO_2") (pintype "bidirectional"))
    )
    (net (code "29") (name "MOSI") (class "Default")
      (node (ref "J2") (pin "3") (pinfunction "CMD_3") (pintype "passive"))
      (node (ref "PQ60_HEADER") (pin "P$31") (pinfunction "MOSI_P$31") (pintype "bidirectional"))
      (node (ref "PQ60_RECEPTACLE") (pin "P$31") (pinfunction "MOSI_P$31") (pintype "bidirectional"))
      (node (ref "U$4") (pin "51") (pinfunction "D11/MOSI_51") (pintype "bidirectional"))
      (node (ref "U1") (pin "3") (pinfunction "MOSI_3") (pintype "input"))
    )
    (net (code "30") (name "NIRQ") (class "Default")
      (node (ref "U$4") (pin "35") (pinfunction "D16/A2/TOUCH_35") (pintype "bidirectional"))
      (node (ref "U1") (pin "14") (pinfunction "DIO0_14") (pintype "bidirectional"))
    )
    (net (code "31") (name "NSEL") (class "Default")
      (node (ref "U$4") (pin "43") (pinfunction "D15/A1/TOUCH_43") (pintype "bidirectional"))
      (node (ref "U1") (pin "5") (pinfunction "NSS_5") (pintype "input"))
    )
    (net (code "32") (name "Net-(D1-PadA)") (class "Default")
      (node (ref "D1") (pin "A") (pinfunction "A_A") (pintype "passive"))
      (node (ref "R7") (pin "1") (pinfunction "1_1") (pintype "passive"))
    )
    (net (code "33") (name "Net-(D2-PadA)") (class "Default")
      (node (ref "D2") (pin "A") (pinfunction "A_A") (pintype "passive"))
      (node (ref "R6") (pin "1") (pinfunction "1_1") (pintype "passive"))
    )
    (net (code "34") (name "Net-(D5-PadA)") (class "Default")
      (node (ref "D5") (pin "A") (pinfunction "A_A") (pintype "passive"))
      (node (ref "R13") (pin "1") (pinfunction "1_1") (pintype "passive"))
    )
    (net (code "35") (name "Net-(J2-PadSW)") (class "Default")
      (node (ref "J2") (pin "SW") (pinfunction "SW_SW") (pintype "passive"))
      (node (ref "R10") (pin "2") (pinfunction "2_2") (pintype "passive"))
    )
    (net (code "36") (name "Net-(J2-VSS)") (class "Default")
      (node (ref "J2") (pin "6") (pinfunction "VSS_6") (pintype "passive"))
      (node (ref "U$3") (pin "3") (pinfunction "D_3") (pintype "bidirectional"))
    )
    (net (code "37") (name "Net-(L3-Pad2)") (class "Default")
      (node (ref "L3") (pin "2") (pinfunction "2_2") (pintype "passive"))
      (node (ref "U$11") (pin "GND@1") (pinfunction "SHIELD_GND@1") (pintype "bidirectional"))
      (node (ref "U$11") (pin "GND@2") (pinfunction "SHIELD_GND@2") (pintype "bidirectional"))
      (node (ref "U$11") (pin "GND@3") (pinfunction "SHIELD_GND@3") (pintype "bidirectional"))
      (node (ref "U$11") (pin "GND@4") (pinfunction "SHIELD_GND@4") (pintype "bidirectional"))
      (node (ref "U$11") (pin "GND@5") (pinfunction "SHIELD_GND@5") (pintype "bidirectional"))
      (node (ref "U$11") (pin "GND@6") (pinfunction "SHIELD_GND@6") (pintype "bidirectional"))
    )
    (net (code "38") (name "Net-(LSM9DS1-C1)") (class "Default")
      (node (ref "C1") (pin "2") (pinfunction "2_2") (pintype "passive"))
      (node (ref "LSM9DS1") (pin "24") (pinfunction "C1_24") (pintype "bidirectional"))
    )
    (net (code "39") (name "Net-(LSM9DS1-CAP)") (class "Default")
      (node (ref "C3") (pin "1") (pinfunction "1_1") (pintype "passive"))
      (node (ref "LSM9DS1") (pin "21") (pinfunction "CAP_21") (pintype "bidirectional"))
    )
    (net (code "40") (name "Net-(LSM9DS1-CS_A{slash}G)") (class "Default")
      (node (ref "LSM9DS1") (pin "7") (pinfunction "CS_A/G_7") (pintype "bidirectional"))
      (node (ref "R16") (pin "1") (pinfunction "1_1") (pintype "passive"))
    )
    (net (code "41") (name "Net-(LSM9DS1-CS_M)") (class "Default")
      (node (ref "LSM9DS1") (pin "8") (pinfunction "CS_M_8") (pintype "bidirectional"))
      (node (ref "R14") (pin "1") (pinfunction "1_1") (pintype "passive"))
    )
    (net (code "42") (name "Net-(LSM9DS1-SDO_A{slash}G)") (class "Default")
      (node (ref "LSM9DS1") (pin "5") (pinfunction "SDO_A/G_5") (pintype "bidirectional"))
      (node (ref "R17") (pin "1") (pinfunction "1_1") (pintype "passive"))
    )
    (net (code "43") (name "Net-(LSM9DS1-SDO_M)") (class "Default")
      (node (ref "LSM9DS1") (pin "6") (pinfunction "SDO_M_6") (pintype "bidirectional"))
      (node (ref "R15") (pin "1") (pinfunction "1_1") (pintype "passive"))
    )
    (net (code "44") (name "Net-(NDK_NX3225SA-P$1)") (class "Default")
      (node (ref "NDK_NX3225SA") (pin "1") (pinfunction "P$1_1") (pintype "bidirectional"))
      (node (ref "TP2") (pin "TP") (pinfunction "TP_TP") (pintype "input"))
      (node (ref "U$4") (pin "32") (pinfunction "OSC1_32") (pintype "bidirectional"))
    )
    (net (code "45") (name "Net-(NDK_NX3225SA-P$2)") (class "Default")
      (node (ref "NDK_NX3225SA") (pin "3") (pinfunction "P$2_3") (pintype "bidirectional"))
      (node (ref "TP1") (pin "TP") (pinfunction "TP_TP") (pintype "input"))
      (node (ref "U$4") (pin "33") (pinfunction "OSC2_33") (pintype "bidirectional"))
    )
    (net (code "46") (name "Net-(U$1-PTA0{slash}IRQ_0)") (class "Default")
      (node (ref "TP15") (pin "TP") (pinfunction "TP_TP") (pintype "input"))
      (node (ref "U$1") (pin "14") (pinfunction "PTA0/IRQ_0_14") (pintype "bidirectional"))
    )
    (net (code "47") (name "Net-(U$1-PTA2)") (class "Default")
      (node (ref "TP16") (pin "TP") (pinfunction "TP_TP") (pintype "input"))
      (node (ref "U$1") (pin "16") (pinfunction "PTA2_16") (pintype "bidirectional"))
    )
    (net (code "48") (name "Net-(U$1-PTA4)") (class "Default")
      (node (ref "RST") (pin "TP") (pinfunction "TP_TP") (pintype "input"))
      (node (ref "U$1") (pin "13") (pinfunction "PTB5/IRQ_12_13") (pintype "bidirectional"))
      (node (ref "U$1") (pin "4") (pinfunction "PTA4_4") (pintype "bidirectional"))
      (node (ref "U$4") (pin "34") (pinfunction "RESET_34") (pintype "bidirectional"))
      (node (ref "U$9") (pin "10") (pinfunction "RESET_10") (pintype "bidirectional"))
    )
    (net (code "49") (name "Net-(U$1-PTB2{slash}IRQ_7)") (class "Default")
      (node (ref "ERASE") (pin "A@1") (pinfunction "P$1_A@1") (pintype "bidirectional"))
      (node (ref "ERASE") (pin "A@2") (pinfunction "P$1_A@2") (pintype "bidirectional"))
      (node (ref "R9") (pin "1") (pinfunction "1_1") (pintype "passive"))
      (node (ref "U$1") (pin "10") (pinfunction "PTB2/IRQ_7_10") (pintype "bidirectional"))
    )
    (net (code "50") (name "Net-(U$1-VDD_VREFH)") (class "Default")
      (node (ref "C9") (pin "1") (pinfunction "1_1") (pintype "passive"))
      (node (ref "SJ3") (pin "P$1") (pinfunction "P$1_P$1") (pintype "bidirectional"))
      (node (ref "U$1") (pin "1") (pinfunction "VDD_VREFH_1") (pintype "bidirectional"))
    )
    (net (code "51") (name "Net-(U$4-D6{slash}PWM)") (class "Default")
      (node (ref "TP5") (pin "TP") (pinfunction "TP_TP") (pintype "input"))
      (node (ref "U$4") (pin "61") (pinfunction "D6/PWM_61") (pintype "bidirectional"))
    )
    (net (code "52") (name "Net-(U$4-D7{slash}RX3)") (class "Default")
      (node (ref "TP6") (pin "TP") (pinfunction "TP_TP") (pintype "input"))
      (node (ref "U$4") (pin "59") (pinfunction "D7/RX3_59") (pintype "bidirectional"))
    )
    (net (code "53") (name "Net-(U$4-D8{slash}TX3)") (class "Default")
      (node (ref "TP7") (pin "TP") (pinfunction "TP_TP") (pintype "input"))
      (node (ref "U$4") (pin "60") (pinfunction "D8/TX3_60") (pintype "bidirectional"))
    )
    (net (code "54") (name "Net-(U$4-D22{slash}A8{slash}PWM{slash}TOUCH)") (class "Default")
      (node (ref "TP8") (pin "TP") (pinfunction "TP_TP") (pintype "input"))
      (node (ref "U$4") (pin "44") (pinfunction "D22/A8/PWM/TOUCH_44") (pintype "bidirectional"))
    )
    (net (code "55") (name "Net-(U$4-D23{slash}A9{slash}PWM{slash}TOUCH)") (class "Default")
      (node (ref "TP9") (pin "TP") (pinfunction "TP_TP") (pintype "input"))
      (node (ref "U$4") (pin "45") (pinfunction "D23/A9/PWM/TOUCH_45") (pintype "bidirectional"))
    )
    (net (code "56") (name "Net-(U$4-EXTAL32)") (class "Default")
      (node (ref "TP3") (pin "TP") (pinfunction "TP_TP") (pintype "input"))
      (node (ref "U$4") (pin "20") (pinfunction "EXTAL32_20") (pintype "bidirectional"))
    )
    (net (code "57") (name "Net-(U$4-VCCA)") (class "Default")
      (node (ref "C15") (pin "1") (pinfunction "1_1") (pintype "passive"))
      (node (ref "L2") (pin "2") (pinfunction "2_2") (pintype "passive"))
      (node (ref "R12") (pin "2") (pinfunction "2_2") (pintype "passive"))
      (node (ref "U$4") (pin "13") (pinfunction "VCCA_13") (pintype "bidirectional"))
    )
    (net (code "58") (name "Net-(U$4-VREF-H)") (class "Default")
      (node (ref "C17") (pin "1") (pinfunction "1_1") (pintype "passive"))
      (node (ref "R12") (pin "1") (pinfunction "1_1") (pintype "passive"))
      (node (ref "U$4") (pin "14") (pinfunction "VREF-H_14") (pintype "bidirectional"))
    )
    (net (code "59") (name "Net-(U$4-VREF-L)") (class "Default")
      (node (ref "C15") (pin "2") (pinfunction "2_2") (pintype "passive"))
      (node (ref "C16") (pin "2") (pinfunction "2_2") (pintype "passive"))
      (node (ref "C17") (pin "2") (pinfunction "2_2") (pintype "passive"))
      (node (ref "L4") (pin "2") (pinfunction "2_2") (pintype "passive"))
      (node (ref "U$4") (pin "15") (pinfunction "VREF-L_15") (pintype "bidirectional"))
      (node (ref "U$4") (pin "16") (pinfunction "VSSA_16") (pintype "bidirectional"))
    )
    (net (code "60") (name "Net-(U$4-VREF_OUT)") (class "Default")
      (node (ref "C16") (pin "1") (pinfunction "1_1") (pintype "passive"))
      (node (ref "U$4") (pin "17") (pinfunction "VREF_OUT_17") (pintype "bidirectional"))
    )
    (net (code "61") (name "Net-(U$4-XTAL32)") (class "Default")
      (node (ref "TP4") (pin "TP") (pinfunction "TP_TP") (pintype "input"))
      (node (ref "U$4") (pin "19") (pinfunction "XTAL32_19") (pintype "bidirectional"))
    )
    (net (code "62") (name "Net-(U$11-D+)") (class "Default")
      (node (ref "R3") (pin "1") (pinfunction "1_1") (pintype "passive"))
      (node (ref "U$11") (pin "P$3") (pinfunction "D+_P$3") (pintype "bidirectional"))
    )
    (net (code "63") (name "Net-(U$11-D-)") (class "Default")
      (node (ref "R1") (pin "1") (pinfunction "1_1") (pintype "passive"))
      (node (ref "U$11") (pin "P$2") (pinfunction "D-_P$2") (pintype "bidirectional"))
    )
    (net (code "64") (name "Net-(U.FL-SIGNAL)") (class "Default")
      (node (ref "U.FL") (pin "P$3") (pinfunction "SIGNAL_P$3") (pintype "bidirectional"))
      (node (ref "U1") (pin "9") (pinfunction "ANT_9") (pintype "passive"))
    )
    (net (code "65") (name "Net-(U1-DIO1)") (class "Default")
      (node (ref "TP10") (pin "TP") (pinfunction "TP_TP") (pintype "input"))
      (node (ref "U1") (pin "15") (pinfunction "DIO1_15") (pintype "bidirectional"))
    )
    (net (code "66") (name "Net-(U1-DIO2)") (class "Default")
      (node (ref "TP11") (pin "TP") (pinfunction "TP_TP") (pintype "input"))
      (node (ref "U1") (pin "16") (pinfunction "DIO2_16") (pintype "bidirectional"))
    )
    (net (code "67") (name "Net-(U1-DIO3)") (class "Default")
      (node (ref "TP12") (pin "TP") (pinfunction "TP_TP") (pintype "input"))
      (node (ref "U1") (pin "11") (pinfunction "DIO3_11") (pintype "bidirectional"))
    )
    (net (code "68") (name "Net-(U1-DIO4)") (class "Default")
      (node (ref "TP13") (pin "TP") (pinfunction "TP_TP") (pintype "input"))
      (node (ref "U1") (pin "12") (pinfunction "DIO4_12") (pintype "bidirectional"))
    )
    (net (code "69") (name "Net-(U1-DIO5)") (class "Default")
      (node (ref "TP14") (pin "TP") (pinfunction "TP_TP") (pintype "input"))
      (node (ref "U1") (pin "7") (pinfunction "DIO5_7") (pintype "bidirectional"))
    )
    (net (code "70") (name "RADIO_RST") (class "Default")
      (node (ref "U$4") (pin "27") (pinfunction "D24_27") (pintype "bidirectional"))
      (node (ref "U1") (pin "6") (pinfunction "RESET_6") (pintype "input"))
    )
    (net (code "71") (name "RESET") (class "Default")
      (node (ref "PQ60_HEADER") (pin "P$27") (pinfunction "/RST_P$27") (pintype "bidirectional"))
      (node (ref "PQ60_RECEPTACLE") (pin "P$27") (pinfunction "/RST_P$27") (pintype "bidirectional"))
    )
    (net (code "72") (name "SCK") (class "Default")
      (node (ref "J2") (pin "5") (pinfunction "CLK_5") (pintype "passive"))
      (node (ref "PQ60_HEADER") (pin "P$33") (pinfunction "SCK_P$33") (pintype "bidirectional"))
      (node (ref "PQ60_RECEPTACLE") (pin "P$33") (pinfunction "SCK_P$33") (pintype "bidirectional"))
      (node (ref "U$4") (pin "50") (pinfunction "D13/SCK/LED_50") (pintype "bidirectional"))
      (node (ref "U1") (pin "4") (pinfunction "SCK_4") (pintype "input"))
    )
    (net (code "73") (name "SCL") (class "Default")
      (node (ref "LSM9DS1") (pin "2") (pinfunction "SCL/SPC_2") (pintype "bidirectional"))
      (node (ref "PQ60_HEADER") (pin "P$29") (pinfunction "SCL_P$29") (pintype "bidirectional"))
      (node (ref "PQ60_RECEPTACLE") (pin "P$29") (pinfunction "SCL_P$29") (pintype "bidirectional"))
      (node (ref "R2") (pin "2") (pinfunction "2_2") (pintype "passive"))
      (node (ref "U$4") (pin "37") (pinfunction "D19/A5/SCL0/TOUCH_37") (pintype "bidirectional"))
    )
    (net (code "74") (name "SDA") (class "Default")
      (node (ref "LSM9DS1") (pin "4") (pinfunction "SDA/SDI/SDO_4") (pintype "bidirectional"))
      (node (ref "PQ60_HEADER") (pin "P$30") (pinfunction "SDA_P$30") (pintype "bidirectional"))
      (node (ref "PQ60_RECEPTACLE") (pin "P$30") (pinfunction "SDA_P$30") (pintype "bidirectional"))
      (node (ref "R8") (pin "2") (pinfunction "2_2") (pintype "passive"))
      (node (ref "U$4") (pin "38") (pinfunction "D18/A4/SDA0/TOUCH_38") (pintype "bidirectional"))
    )
    (net (code "75") (name "SD_POWER") (class "Default")
      (node (ref "R11") (pin "1") (pinfunction "1_1") (pintype "passive"))
      (node (ref "U$3") (pin "1") (pinfunction "G_1") (pintype "bidirectional"))
      (node (ref "U$4") (pin "2") (pinfunction "D26/A15_2") (pintype "bidirectional"))
    )
    (net (code "76") (name "SWDCLK") (class "Default")
      (node (ref "PTA0") (pin "TP") (pinfunction "TP_TP") (pintype "input"))
      (node (ref "U$1") (pin "8") (pinfunction "PTB0/IRQ_5_8") (pintype "bidirectional"))
      (node (ref "U$4") (pin "22") (pinfunction "PTA0_22") (pintype "bidirectional"))
      (node (ref "U$9") (pin "4") (pinfunction "SWDCLK_4") (pintype "bidirectional"))
    )
    (net (code "77") (name "SWDIO") (class "Default")
      (node (ref "PTA3") (pin "TP") (pinfunction "TP_TP") (pintype "input"))
      (node (ref "U$1") (pin "7") (pinfunction "PTA7/IRQ_4_7") (pintype "bidirectional"))
      (node (ref "U$4") (pin "25") (pinfunction "PTA3_25") (pintype "bidirectional"))
      (node (ref "U$9") (pin "2") (pinfunction "SWDIO_2") (pintype "bidirectional"))
    )
    (net (code "78") (name "SWO") (class "Default")
      (node (ref "PTA2") (pin "TP") (pinfunction "TP_TP") (pintype "input"))
      (node (ref "U$1") (pin "9") (pinfunction "PTB1/IRQ_6_9") (pintype "bidirectional"))
      (node (ref "U$4") (pin "24") (pinfunction "PTA2_24") (pintype "bidirectional"))
      (node (ref "U$9") (pin "6") (pinfunction "SWO_6") (pintype "bidirectional"))
    )
    (net (code "79") (name "USB_D_N") (class "Default")
      (node (ref "R1") (pin "2") (pinfunction "2_2") (pintype "passive"))
      (node (ref "U$4") (pin "6") (pinfunction "USB-M_6") (pintype "bidirectional"))
    )
    (net (code "80") (name "USB_D_P") (class "Default")
      (node (ref "R3") (pin "2") (pinfunction "2_2") (pintype "passive"))
      (node (ref "U$4") (pin "5") (pinfunction "USB-P_5") (pintype "bidirectional"))
    )
    (net (code "81") (name "USB_VBUS") (class "Default")
      (node (ref "PQ60_HEADER") (pin "P$21") (pinfunction "BATV_SW3_P$21") (pintype "power_in"))
      (node (ref "PQ60_HEADER") (pin "P$22") (pinfunction "BATV_SW3_P$22") (pintype "power_in"))
      (node (ref "PQ60_RECEPTACLE") (pin "P$21") (pinfunction "BATV_SW3_P$21") (pintype "power_in"))
      (node (ref "PQ60_RECEPTACLE") (pin "P$22") (pinfunction "BATV_SW3_P$22") (pintype "power_in"))
      (node (ref "U$11") (pin "P$1") (pinfunction "VCC_P$1") (pintype "bidirectional"))
    )
    (net (code "82") (name "unconnected-(J2-DATA1-Pad8)") (class "Default")
      (node (ref "J2") (pin "8") (pinfunction "DATA1_8") (pintype "passive"))
    )
    (net (code "83") (name "unconnected-(J2-DATA2-Pad1)") (class "Default")
      (node (ref "J2") (pin "1") (pinfunction "DATA2_1") (pintype "passive"))
    )
    (net (code "84") (name "unconnected-(LSM9DS1-DEN_A{slash}G-Pad13)") (class "Default")
      (node (ref "LSM9DS1") (pin "13") (pinfunction "DEN_A/G_13") (pintype "bidirectional"))
    )
    (net (code "85") (name "unconnected-(LSM9DS1-DRDY_M-Pad9)") (class "Default")
      (node (ref "LSM9DS1") (pin "9") (pinfunction "DRDY_M_9") (pintype "bidirectional"))
    )
    (net (code "86") (name "unconnected-(LSM9DS1-INT1_A{slash}G-Pad11)") (class "Default")
      (node (ref "LSM9DS1") (pin "11") (pinfunction "INT1_A/G_11") (pintype "bidirectional"))
    )
    (net (code "87") (name "unconnected-(LSM9DS1-INT2_A{slash}G-Pad12)") (class "Default")
      (node (ref "LSM9DS1") (pin "12") (pinfunction "INT2_A/G_12") (pintype "bidirectional"))
    )
    (net (code "88") (name "unconnected-(LSM9DS1-INT_M-Pad10)") (class "Default")
      (node (ref "LSM9DS1") (pin "10") (pinfunction "INT_M_10") (pintype "bidirectional"))
    )
    (net (code "89") (name "unconnected-(U$1-PTA1{slash}IRQ_1{slash}LPTMR0_ALT1-Pad15)") (class "Default")
      (node (ref "U$1") (pin "15") (pinfunction "PTA1/IRQ_1/LPTMR0_ALT1_15") (pintype "bidirectional"))
    )
    (net (code "90") (name "unconnected-(U$1-PTA3-Pad3)") (class "Default")
      (node (ref "U$1") (pin "3") (pinfunction "PTA3_3") (pintype "bidirectional"))
    )
    (net (code "91") (name "unconnected-(U$1-PTA5-Pad5)") (class "Default")
      (node (ref "U$1") (pin "5") (pinfunction "PTA5_5") (pintype "bidirectional"))
    )
    (net (code "92") (name "unconnected-(U$1-PTB3{slash}IRQ_10-Pad11)") (class "Default")
      (node (ref "U$1") (pin "11") (pinfunction "PTB3/IRQ_10_11") (pintype "bidirectional"))
    )
    (net (code "93") (name "unconnected-(U$1-PTB4{slash}IRQ_11-Pad12)") (class "Default")
      (node (ref "U$1") (pin "12") (pinfunction "PTB4/IRQ_11_12") (pintype "bidirectional"))
    )
    (net (code "94") (name "unconnected-(U$4-A10{slash}ADC0_DM0-Pad10)") (class "Default")
      (node (ref "U$4") (pin "10") (pinfunction "A10/ADC0_DM0_10") (pintype "bidirectional"))
    )
    (net (code "95") (name "unconnected-(U$4-A11{slash}ADC0_DP0-Pad9)") (class "Default")
      (node (ref "U$4") (pin "9") (pinfunction "A11/ADC0_DP0_9") (pintype "bidirectional"))
    )
    (net (code "96") (name "unconnected-(U$4-D14{slash}A0-Pad58)") (class "Default")
      (node (ref "U$4") (pin "58") (pinfunction "D14/A0_58") (pintype "bidirectional"))
    )
    (net (code "97") (name "unconnected-(U$4-D17{slash}A3{slash}TOUCH-Pad36)") (class "Default")
      (node (ref "U$4") (pin "36") (pinfunction "D17/A3/TOUCH_36") (pintype "bidirectional"))
    )
    (net (code "98") (name "unconnected-(U$4-D25{slash}PWM{slash}TOUCH-Pad42)") (class "Default")
      (node (ref "U$4") (pin "42") (pinfunction "D25/PWM/TOUCH_42") (pintype "bidirectional"))
    )
    (net (code "99") (name "unconnected-(U$4-D27{slash}A16-Pad54)") (class "Default")
      (node (ref "U$4") (pin "54") (pinfunction "D27/A16_54") (pintype "bidirectional"))
    )
    (net (code "100") (name "unconnected-(U$4-D28{slash}A17-Pad53)") (class "Default")
      (node (ref "U$4") (pin "53") (pinfunction "D28/A17_53") (pintype "bidirectional"))
    )
    (net (code "101") (name "unconnected-(U$9-GND_DET-Pad9)") (class "Default")
      (node (ref "U$9") (pin "9") (pinfunction "GND_DET_9") (pintype "bidirectional"))
    )
    (net (code "102") (name "unconnected-(U$9-KEY-Pad7)") (class "Default")
      (node (ref "U$9") (pin "7") (pinfunction "KEY_7") (pintype "bidirectional"))
    )
    (net (code "103") (name "unconnected-(U$9-NC-Pad8)") (class "Default")
      (node (ref "U$9") (pin "8") (pinfunction "NC_8") (pintype "bidirectional"))
    )
  )
)
